# w27-USBIO-v03_rev2_3.net
KiCad netlist of a schematic drawn in EAGLE
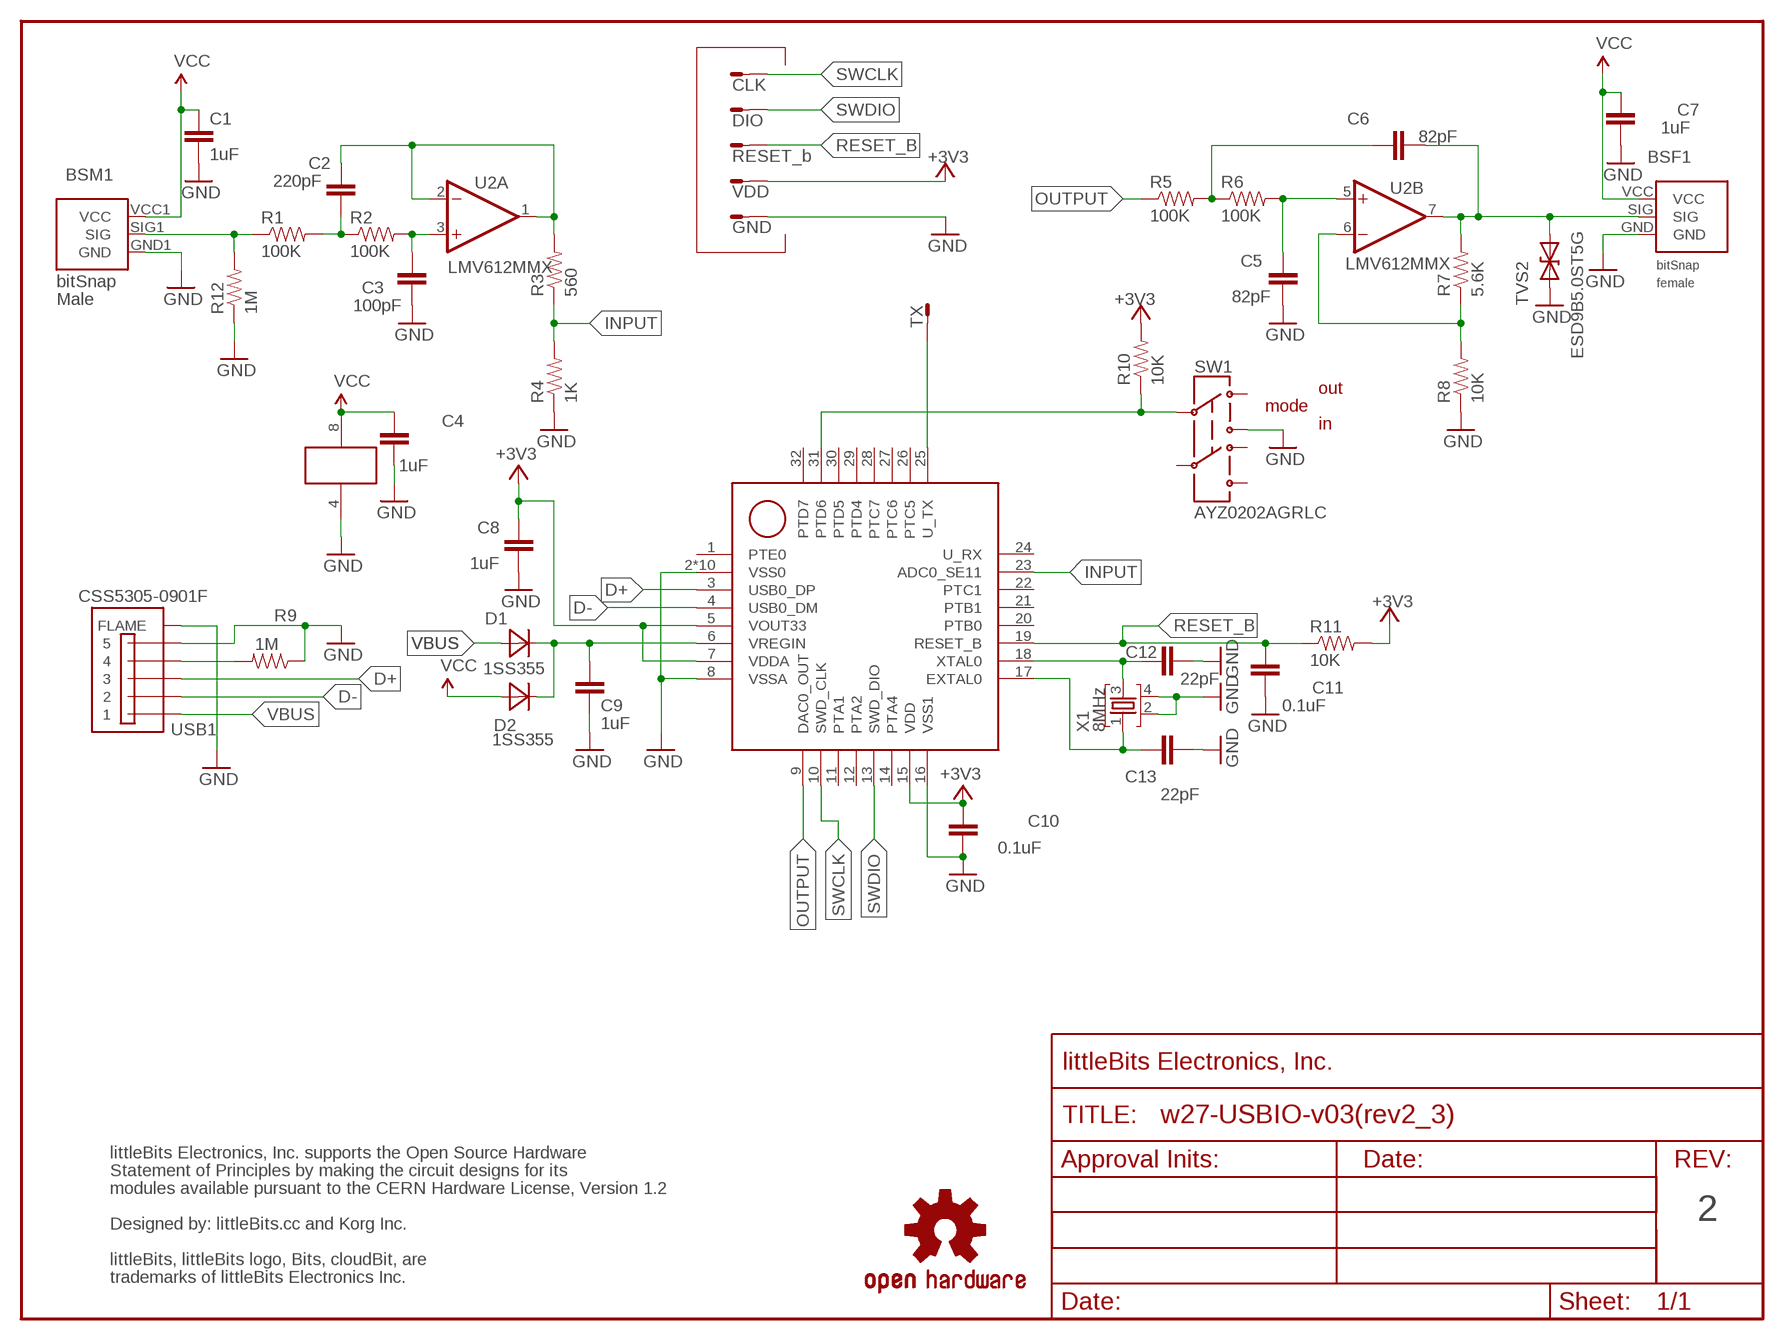
[diagram p0: schematic, sheet 1]

(export (version "E")
  (design (tool "Eeschema 10.0.6"))
  (components
    (comp (ref "BSF1")
      (value "BITSNAP_V03_FEMALE")
      (footprint "eagle-import:BITSNAP_V03_FEMALE")
      (libsource (lib "eagle-import") (part "BITSNAP_V03_FEMALE"))
    )
    (comp (ref "BSM1")
      (value "BITSNAP_V03_MALE")
      (footprint "eagle-import:BITSNAP_V03_MALE")
      (libsource (lib "eagle-import") (part "BITSNAP_V03_MALE"))
    )
    (comp (ref "C1")
      (value "1uF")
      (footprint "eagle-import:CC_1608_0.8_TBR_LB_1PRIMARY")
      (libsource (lib "eagle-import") (part "CC_1608_0.8_TBR_LB_1"))
    )
    (comp (ref "C2")
      (value "220pF")
      (footprint "eagle-import:CC_1608_0.8_TBR_LB_1PRIMARY")
      (libsource (lib "eagle-import") (part "CC_1608_0.8_TBR_LB_1"))
    )
    (comp (ref "C3")
      (value "100pF")
      (footprint "eagle-import:CC_1608_0.8_TBR_LB_1PRIMARY")
      (libsource (lib "eagle-import") (part "CC_1608_0.8_TBR_LB_1"))
    )
    (comp (ref "C4")
      (value "1uF")
      (footprint "eagle-import:CC_1608_0.8_TBR_LB_1PRIMARY")
      (libsource (lib "eagle-import") (part "CC_1608_0.8_TBR_LB_1"))
    )
    (comp (ref "C5")
      (value "82pF")
      (footprint "eagle-import:CC_1608_0.8_TBR_LB_1PRIMARY")
      (libsource (lib "eagle-import") (part "CC_1608_0.8_TBR_LB_1"))
    )
    (comp (ref "C6")
      (value "82pF")
      (footprint "eagle-import:CC_1608_0.8_TBR_LB_1PRIMARY")
      (libsource (lib "eagle-import") (part "CC_1608_0.8_TBR_LB_1"))
    )
    (comp (ref "C7")
      (value "1uF")
      (footprint "eagle-import:CC_1608_0.8_TBR_LB_1PRIMARY")
      (libsource (lib "eagle-import") (part "CC_1608_0.8_TBR_LB_1"))
    )
    (comp (ref "C8")
      (value "1uF")
      (footprint "eagle-import:CC_1608_0.8_TBR_LB_1PRIMARY")
      (libsource (lib "eagle-import") (part "CC_1608_0.8_TBR_LB_1"))
    )
    (comp (ref "C9")
      (value "1uF")
      (footprint "eagle-import:CC_1608_0.8_TBR_LB_1PRIMARY")
      (libsource (lib "eagle-import") (part "CC_1608_0.8_TBR_LB_1"))
    )
    (comp (ref "C10")
      (value "0.1uF")
      (footprint "eagle-import:CC_1608_0.8_TBR_LB_1PRIMARY")
      (libsource (lib "eagle-import") (part "CC_1608_0.8_TBR_LB_1"))
    )
    (comp (ref "C11")
      (value "0.1uF")
      (footprint "eagle-import:CC_1608_0.8_TBR_LB_1PRIMARY")
      (libsource (lib "eagle-import") (part "CC_1608_0.8_TBR_LB_1"))
    )
    (comp (ref "C12")
      (value "22pF")
      (footprint "eagle-import:CC_1608_0.8_TBR_LB_1PRIMARY")
      (libsource (lib "eagle-import") (part "CC_1608_0.8_TBR_LB_1"))
    )
    (comp (ref "C13")
      (value "22pF")
      (footprint "eagle-import:CC_1608_0.8_TBR_LB_1PRIMARY")
      (libsource (lib "eagle-import") (part "CC_1608_0.8_TBR_LB_1"))
    )
    (comp (ref "D1")
      (value "1SS355")
      (footprint "eagle-import:DISC_ROHM-UMD2_#_TBR_LB_1PRIMARY")
      (libsource (lib "eagle-import") (part "DISC_ROHM-UMD2_#_TBR_LB_1"))
    )
    (comp (ref "D2")
      (value "1SS355")
      (footprint "eagle-import:DISC_ROHM-UMD2_#_TBR_LB_1PRIMARY")
      (libsource (lib "eagle-import") (part "DISC_ROHM-UMD2_#_TBR_LB_1"))
    )
    (comp (ref "FRAME1")
      (value "FRAME-LETTER-OHWOHW")
      (footprint "eagle-import:FABDWG01-OHW")
      (libsource (lib "eagle-import") (part "FRAME-LETTER-OHWOHW"))
    )
    (comp (ref "JP1")
      (value "GND")
      (footprint "eagle-import:TEST_POINT_1PRIMARY")
      (libsource (lib "eagle-import") (part "TEST_POINT_1"))
    )
    (comp (ref "JP2")
      (value "VDD")
      (footprint "eagle-import:TEST_POINT_1PRIMARY")
      (libsource (lib "eagle-import") (part "TEST_POINT_1"))
    )
    (comp (ref "JP3")
      (value "RESET_b")
      (footprint "eagle-import:TEST_POINT_1PRIMARY")
      (libsource (lib "eagle-import") (part "TEST_POINT_1"))
    )
    (comp (ref "JP4")
      (value "DIO")
      (footprint "eagle-import:TEST_POINT_1PRIMARY")
      (libsource (lib "eagle-import") (part "TEST_POINT_1"))
    )
    (comp (ref "JP5")
      (value "CLK")
      (footprint "eagle-import:TEST_POINT_1PRIMARY")
      (libsource (lib "eagle-import") (part "TEST_POINT_1"))
    )
    (comp (ref "JP6")
      (value "TX")
      (footprint "eagle-import:TEST_POINT_1PRIMARY")
      (libsource (lib "eagle-import") (part "TEST_POINT_1"))
    )
    (comp (ref "R1")
      (value "100K")
      (footprint "eagle-import:R_1608_LB")
      (libsource (lib "eagle-import") (part "R_1608_LB"))
    )
    (comp (ref "R2")
      (value "100K")
      (footprint "eagle-import:R_1608_LB")
      (libsource (lib "eagle-import") (part "R_1608_LB"))
    )
    (comp (ref "R3")
      (value "560")
      (footprint "eagle-import:R_1608_LB")
      (libsource (lib "eagle-import") (part "R_1608_LB"))
    )
    (comp (ref "R4")
      (value "1K")
      (footprint "eagle-import:R_1608_LB")
      (libsource (lib "eagle-import") (part "R_1608_LB"))
    )
    (comp (ref "R5")
      (value "100K")
      (footprint "eagle-import:R_1608_LB")
      (libsource (lib "eagle-import") (part "R_1608_LB"))
    )
    (comp (ref "R6")
      (value "100K")
      (footprint "eagle-import:R_1608_LB")
      (libsource (lib "eagle-import") (part "R_1608_LB"))
    )
    (comp (ref "R7")
      (value "5.6K")
      (footprint "eagle-import:R_1608_LB")
      (libsource (lib "eagle-import") (part "R_1608_LB"))
    )
    (comp (ref "R8")
      (value "10K")
      (footprint "eagle-import:R_1608_LB")
      (libsource (lib "eagle-import") (part "R_1608_LB"))
    )
    (comp (ref "R9")
      (value "1M")
      (footprint "eagle-import:R_1608_LB")
      (libsource (lib "eagle-import") (part "R_1608_LB"))
    )
    (comp (ref "R10")
      (value "10K")
      (footprint "eagle-import:R_1608_LB")
      (libsource (lib "eagle-import") (part "R_1608_LB"))
    )
    (comp (ref "R11")
      (value "10K")
      (footprint "eagle-import:R_1608_LB")
      (libsource (lib "eagle-import") (part "R_1608_LB"))
    )
    (comp (ref "R12")
      (value "1M")
      (footprint "eagle-import:RES-0402")
      (libsource (lib "eagle-import") (part "RESISTOR0402"))
    )
    (comp (ref "SW1")
      (value "AYZ0202AGRLC")
      (footprint "eagle-import:SW_MS-22C01_#_TBR_LB_1PRIMARY")
      (libsource (lib "eagle-import") (part "SW_MS-22C01_#_TBR_LB_1"))
    )
    (comp (ref "TVS2")
      (value "ESD9B5.0ST5G")
      (footprint "eagle-import:SOD-923")
      (libsource (lib "eagle-import") (part "DIODE-TVSSOD-923"))
    )
    (comp (ref "U$1")
      (value "OSHWCREDIT-KORG")
      (footprint "eagle-import:OSHWCREDIT-KORG")
      (libsource (lib "eagle-import") (part "OSHWCREDIT-KORG"))
    )
    (comp (ref "U$5")
      (value "OSHW-LOGOL")
      (footprint "eagle-import:OSHW-LOGO-L")
      (libsource (lib "eagle-import") (part "OSHW-LOGOL"))
    )
    (comp (ref "U1")
      (value "MKL26Z64VFM4")
      (footprint "eagle-import:IC_TI-QFN32_0.5_TBR_LB_1PRIMARY")
      (libsource (lib "eagle-import") (part "IC_TI-QFN32_0.5_TBR_LB_1"))
    )
    (comp (ref "U2")
      (value "LMV612MMX")
      (footprint "eagle-import:IC_TSSOP8-DCK_0.65_TBR_LB_1PRIMARY")
      (libsource (lib "eagle-import") (part "IC_TSSOP8-DCK_0.65_TBR_LB_1"))
    )
    (comp (ref "USB1")
      (value "CSS5305-0901F")
      (footprint "eagle-import:MICRO-USB-FRONT-DIP-REAR-SMD")
      (libsource (lib "eagle-import") (part "CSS5305-0109F"))
    )
    (comp (ref "X1")
      (value "8MHz")
      (footprint "eagle-import:X_ROSON_RT5_#_TBR_LB_1PRIMARY")
      (libsource (lib "eagle-import") (part "X_ROSON_RT5_#_TBR_LB_1"))
    )
  )
  (nets
    (net (code "1") (name "+3V3") (class "Default")
      (node (ref "C10") (pin "2") (pinfunction "2_2") (pintype "passive"))
      (node (ref "C8") (pin "2") (pinfunction "2_2") (pintype "passive"))
      (node (ref "JP2") (pin "1") (pinfunction "S_1") (pintype "passive"))
      (node (ref "R10") (pin "2") (pinfunction "2_2") (pintype "passive"))
      (node (ref "R11") (pin "2") (pinfunction "2_2") (pintype "passive"))
      (node (ref "U1") (pin "15") (pinfunction "VDD_15") (pintype "bidirectional"))
      (node (ref "U1") (pin "5") (pinfunction "VOUT33_5") (pintype "bidirectional"))
      (node (ref "U1") (pin "7") (pinfunction "VDDA_7") (pintype "bidirectional"))
    )
    (net (code "2") (name "D+") (class "Default")
      (node (ref "U1") (pin "3") (pinfunction "USB0_DP_3") (pintype "bidirectional"))
      (node (ref "USB1") (pin "3") (pinfunction "3_3") (pintype "input"))
    )
    (net (code "3") (name "D-") (class "Default")
      (node (ref "U1") (pin "4") (pinfunction "USB0_DM_4") (pintype "bidirectional"))
      (node (ref "USB1") (pin "2") (pinfunction "2_2") (pintype "input"))
    )
    (net (code "4") (name "GND") (class "Default")
      (node (ref "BSF1") (pin "GND") (pinfunction "GND_GND") (pintype "bidirectional"))
      (node (ref "BSM1") (pin "GND1") (pinfunction "GND_GND1") (pintype "bidirectional"))
      (node (ref "C1") (pin "2") (pinfunction "2_2") (pintype "passive"))
      (node (ref "C10") (pin "1") (pinfunction "1_1") (pintype "passive"))
      (node (ref "C11") (pin "1") (pinfunction "1_1") (pintype "passive"))
      (node (ref "C12") (pin "1") (pinfunction "1_1") (pintype "passive"))
      (node (ref "C13") (pin "1") (pinfunction "1_1") (pintype "passive"))
      (node (ref "C3") (pin "1") (pinfunction "1_1") (pintype "passive"))
      (node (ref "C4") (pin "1") (pinfunction "1_1") (pintype "passive"))
      (node (ref "C5") (pin "1") (pinfunction "1_1") (pintype "passive"))
      (node (ref "C7") (pin "1") (pinfunction "1_1") (pintype "passive"))
      (node (ref "C8") (pin "1") (pinfunction "1_1") (pintype "passive"))
      (node (ref "C9") (pin "2") (pinfunction "2_2") (pintype "passive"))
      (node (ref "JP1") (pin "1") (pinfunction "S_1") (pintype "passive"))
      (node (ref "R12") (pin "1") (pinfunction "1_1") (pintype "passive"))
      (node (ref "R4") (pin "1") (pinfunction "1_1") (pintype "passive"))
      (node (ref "R8") (pin "1") (pinfunction "1_1") (pintype "passive"))
      (node (ref "R9") (pin "1") (pinfunction "1_1") (pintype "passive"))
      (node (ref "SW1") (pin "3") (pinfunction "3_3") (pintype "bidirectional"))
      (node (ref "TVS2") (pin "1") (pinfunction "A_1") (pintype "passive"))
      (node (ref "U1") (pin "16") (pinfunction "VSS1_16") (pintype "bidirectional"))
      (node (ref "U1") (pin "2") (pinfunction "VSS0_2") (pintype "bidirectional"))
      (node (ref "U1") (pin "33") (pinfunction "VSS0_33") (pintype "bidirectional"))
      (node (ref "U1") (pin "34") (pinfunction "VSS0_34") (pintype "bidirectional"))
      (node (ref "U1") (pin "35") (pinfunction "VSS0_35") (pintype "bidirectional"))
      (node (ref "U1") (pin "36") (pinfunction "VSS0_36") (pintype "bidirectional"))
      (node (ref "U1") (pin "37") (pinfunction "VSS0_37") (pintype "bidirectional"))
      (node (ref "U1") (pin "38") (pinfunction "VSS0_38") (pintype "bidirectional"))
      (node (ref "U1") (pin "39") (pinfunction "VSS0_39") (pintype "bidirectional"))
      (node (ref "U1") (pin "40") (pinfunction "VSS0_40") (pintype "bidirectional"))
      (node (ref "U1") (pin "41") (pinfunction "VSS0_41") (pintype "bidirectional"))
      (node (ref "U1") (pin "8") (pinfunction "VSSA_8") (pintype "bidirectional"))
      (node (ref "U2") (pin "4") (pinfunction "V-_4") (pintype "power_in"))
      (node (ref "USB1") (pin "10") (pinfunction "FLAME_10") (pintype "power_in"))
      (node (ref "USB1") (pin "11") (pinfunction "FLAME_11") (pintype "power_in"))
      (node (ref "USB1") (pin "5") (pinfunction "5_5") (pintype "input"))
      (node (ref "USB1") (pin "6") (pinfunction "FLAME_6") (pintype "power_in"))
      (node (ref "USB1") (pin "7") (pinfunction "FLAME_7") (pintype "power_in"))
      (node (ref "USB1") (pin "8") (pinfunction "FLAME_8") (pintype "power_in"))
      (node (ref "USB1") (pin "9") (pinfunction "FLAME_9") (pintype "power_in"))
      (node (ref "X1") (pin "2") (pinfunction "2_2") (pintype "passive"))
      (node (ref "X1") (pin "4") (pinfunction "4_4") (pintype "passive"))
    )
    (net (code "5") (name "INPUT") (class "Default")
      (node (ref "R3") (pin "1") (pinfunction "1_1") (pintype "passive"))
      (node (ref "R4") (pin "2") (pinfunction "2_2") (pintype "passive"))
      (node (ref "U1") (pin "23") (pinfunction "ADC0_SE11_23") (pintype "bidirectional"))
    )
    (net (code "6") (name "Net-(BSM1-SIG)") (class "Default")
      (node (ref "BSM1") (pin "SIG1") (pinfunction "SIG_SIG1") (pintype "bidirectional"))
      (node (ref "R1") (pin "1") (pinfunction "1_1") (pintype "passive"))
      (node (ref "R12") (pin "2") (pinfunction "2_2") (pintype "passive"))
    )
    (net (code "7") (name "Net-(C2-Pad1)") (class "Default")
      (node (ref "C2") (pin "1") (pinfunction "1_1") (pintype "passive"))
      (node (ref "R1") (pin "2") (pinfunction "2_2") (pintype "passive"))
      (node (ref "R2") (pin "1") (pinfunction "1_1") (pintype "passive"))
    )
    (net (code "8") (name "Net-(C6-Pad1)") (class "Default")
      (node (ref "C6") (pin "1") (pinfunction "1_1") (pintype "passive"))
      (node (ref "R5") (pin "2") (pinfunction "2_2") (pintype "passive"))
      (node (ref "R6") (pin "1") (pinfunction "1_1") (pintype "passive"))
    )
    (net (code "9") (name "Net-(JP6-S)") (class "Default")
      (node (ref "JP6") (pin "1") (pinfunction "S_1") (pintype "passive"))
      (node (ref "U1") (pin "25") (pinfunction "U_TX_25") (pintype "bidirectional"))
    )
    (net (code "10") (name "Net-(R9-Pad2)") (class "Default")
      (node (ref "R9") (pin "2") (pinfunction "2_2") (pintype "passive"))
      (node (ref "USB1") (pin "4") (pinfunction "4_4") (pintype "input"))
    )
    (net (code "11") (name "Net-(TVS2-C)") (class "Default")
      (node (ref "BSF1") (pin "SIG") (pinfunction "SIG_SIG") (pintype "bidirectional"))
      (node (ref "C6") (pin "2") (pinfunction "2_2") (pintype "passive"))
      (node (ref "R7") (pin "2") (pinfunction "2_2") (pintype "passive"))
      (node (ref "TVS2") (pin "2") (pinfunction "C_2") (pintype "passive"))
      (node (ref "U2") (pin "7") (pinfunction "OUT_7") (pintype "output"))
    )
    (net (code "12") (name "Net-(U1-EXTAL0)") (class "Default")
      (node (ref "C13") (pin "2") (pinfunction "2_2") (pintype "passive"))
      (node (ref "U1") (pin "17") (pinfunction "EXTAL0_17") (pintype "bidirectional"))
      (node (ref "X1") (pin "1") (pinfunction "1_1") (pintype "passive"))
    )
    (net (code "13") (name "Net-(U1-PTD6)") (class "Default")
      (node (ref "R10") (pin "1") (pinfunction "1_1") (pintype "passive"))
      (node (ref "SW1") (pin "2") (pinfunction "2_2") (pintype "bidirectional"))
      (node (ref "U1") (pin "31") (pinfunction "PTD6_31") (pintype "bidirectional"))
    )
    (net (code "14") (name "Net-(U1-VREGIN)") (class "Default")
      (node (ref "C9") (pin "1") (pinfunction "1_1") (pintype "passive"))
      (node (ref "D1") (pin "2") (pinfunction "2_2") (pintype "passive"))
      (node (ref "D2") (pin "2") (pinfunction "2_2") (pintype "passive"))
      (node (ref "U1") (pin "6") (pinfunction "VREGIN_6") (pintype "bidirectional"))
    )
    (net (code "15") (name "Net-(U1-XTAL0)") (class "Default")
      (node (ref "C12") (pin "2") (pinfunction "2_2") (pintype "passive"))
      (node (ref "U1") (pin "18") (pinfunction "XTAL0_18") (pintype "bidirectional"))
      (node (ref "X1") (pin "3") (pinfunction "3_3") (pintype "passive"))
    )
    (net (code "16") (name "Net-(U2A-+IN)") (class "Default")
      (node (ref "C3") (pin "2") (pinfunction "2_2") (pintype "passive"))
      (node (ref "R2") (pin "2") (pinfunction "2_2") (pintype "passive"))
      (node (ref "U2") (pin "3") (pinfunction "+IN_3") (pintype "input"))
    )
    (net (code "17") (name "Net-(U2A--IN)") (class "Default")
      (node (ref "C2") (pin "2") (pinfunction "2_2") (pintype "passive"))
      (node (ref "R3") (pin "2") (pinfunction "2_2") (pintype "passive"))
      (node (ref "U2") (pin "1") (pinfunction "OUT_1") (pintype "output"))
      (node (ref "U2") (pin "2") (pinfunction "-IN_2") (pintype "input"))
    )
    (net (code "18") (name "Net-(U2B-+IN)") (class "Default")
      (node (ref "C5") (pin "2") (pinfunction "2_2") (pintype "passive"))
      (node (ref "R6") (pin "2") (pinfunction "2_2") (pintype "passive"))
      (node (ref "U2") (pin "5") (pinfunction "+IN_5") (pintype "input"))
    )
    (net (code "19") (name "Net-(U2B--IN)") (class "Default")
      (node (ref "R7") (pin "1") (pinfunction "1_1") (pintype "passive"))
      (node (ref "R8") (pin "2") (pinfunction "2_2") (pintype "passive"))
      (node (ref "U2") (pin "6") (pinfunction "-IN_6") (pintype "input"))
    )
    (net (code "20") (name "OUTPUT") (class "Default")
      (node (ref "R5") (pin "1") (pinfunction "1_1") (pintype "passive"))
      (node (ref "U1") (pin "9") (pinfunction "DAC0_OUT_9") (pintype "bidirectional"))
    )
    (net (code "21") (name "RESET_B") (class "Default")
      (node (ref "C11") (pin "2") (pinfunction "2_2") (pintype "passive"))
      (node (ref "JP3") (pin "1") (pinfunction "S_1") (pintype "passive"))
      (node (ref "R11") (pin "1") (pinfunction "1_1") (pintype "passive"))
      (node (ref "U1") (pin "19") (pinfunction "RESET_B_19") (pintype "bidirectional"))
    )
    (net (code "22") (name "SWCLK") (class "Default")
      (node (ref "JP5") (pin "1") (pinfunction "S_1") (pintype "passive"))
      (node (ref "U1") (pin "10") (pinfunction "SWD_CLK_10") (pintype "bidirectional"))
    )
    (net (code "23") (name "SWDIO") (class "Default")
      (node (ref "JP4") (pin "1") (pinfunction "S_1") (pintype "passive"))
      (node (ref "U1") (pin "13") (pinfunction "SWD_DIO_13") (pintype "bidirectional"))
    )
    (net (code "24") (name "VBUS") (class "Default")
      (node (ref "D1") (pin "1") (pinfunction "1_1") (pintype "passive"))
      (node (ref "USB1") (pin "1") (pinfunction "1_1") (pintype "input"))
    )
    (net (code "25") (name "VCC") (class "Default")
      (node (ref "BSF1") (pin "VCC") (pinfunction "VCC_VCC") (pintype "bidirectional"))
      (node (ref "BSM1") (pin "VCC1") (pinfunction "VCC_VCC1") (pintype "bidirectional"))
      (node (ref "C1") (pin "1") (pinfunction "1_1") (pintype "passive"))
      (node (ref "C4") (pin "2") (pinfunction "2_2") (pintype "passive"))
      (node (ref "C7") (pin "2") (pinfunction "2_2") (pintype "passive"))
      (node (ref "D2") (pin "1") (pinfunction "1_1") (pintype "passive"))
      (node (ref "U2") (pin "8") (pinfunction "V+_8") (pintype "power_in"))
    )
    (net (code "26") (name "unconnected-(SW1-Pad1)") (class "Default")
      (node (ref "SW1") (pin "1") (pinfunction "1_1") (pintype "bidirectional"))
    )
    (net (code "27") (name "unconnected-(SW1-Pad4)") (class "Default")
      (node (ref "SW1") (pin "4") (pinfunction "4_4") (pintype "bidirectional"))
    )
    (net (code "28") (name "unconnected-(SW1-Pad5)") (class "Default")
      (node (ref "SW1") (pin "5") (pinfunction "5_5") (pintype "bidirectional"))
    )
    (net (code "29") (name "unconnected-(SW1-Pad6)") (class "Default")
      (node (ref "SW1") (pin "6") (pinfunction "6_6") (pintype "bidirectional"))
    )
    (net (code "30") (name "unconnected-(U1-PTA1-Pad11)") (class "Default")
      (node (ref "U1") (pin "11") (pinfunction "PTA1_11") (pintype "bidirectional"))
    )
    (net (code "31") (name "unconnected-(U1-PTA2-Pad12)") (class "Default")
      (node (ref "U1") (pin "12") (pinfunction "PTA2_12") (pintype "bidirectional"))
    )
    (net (code "32") (name "unconnected-(U1-PTA4-Pad14)") (class "Default")
      (node (ref "U1") (pin "14") (pinfunction "PTA4_14") (pintype "bidirectional"))
    )
    (net (code "33") (name "unconnected-(U1-PTB0-Pad20)") (class "Default")
      (node (ref "U1") (pin "20") (pinfunction "PTB0_20") (pintype "bidirectional"))
    )
    (net (code "34") (name "unconnected-(U1-PTB1-Pad21)") (class "Default")
      (node (ref "U1") (pin "21") (pinfunction "PTB1_21") (pintype "bidirectional"))
    )
    (net (code "35") (name "unconnected-(U1-PTC1-Pad22)") (class "Default")
      (node (ref "U1") (pin "22") (pinfunction "PTC1_22") (pintype "bidirectional"))
    )
    (net (code "36") (name "unconnected-(U1-PTC5-Pad26)") (class "Default")
      (node (ref "U1") (pin "26") (pinfunction "PTC5_26") (pintype "bidirectional"))
    )
    (net (code "37") (name "unconnected-(U1-PTC6-Pad27)") (class "Default")
      (node (ref "U1") (pin "27") (pinfunction "PTC6_27") (pintype "bidirectional"))
    )
    (net (code "38") (name "unconnected-(U1-PTC7-Pad28)") (class "Default")
      (node (ref "U1") (pin "28") (pinfunction "PTC7_28") (pintype "bidirectional"))
    )
    (net (code "39") (name "unconnected-(U1-PTD4-Pad29)") (class "Default")
      (node (ref "U1") (pin "29") (pinfunction "PTD4_29") (pintype "bidirectional"))
    )
    (net (code "40") (name "unconnected-(U1-PTD5-Pad30)") (class "Default")
      (node (ref "U1") (pin "30") (pinfunction "PTD5_30") (pintype "bidirectional"))
    )
    (net (code "41") (name "unconnected-(U1-PTD7-Pad32)") (class "Default")
      (node (ref "U1") (pin "32") (pinfunction "PTD7_32") (pintype "bidirectional"))
    )
    (net (code "42") (name "unconnected-(U1-PTE0-Pad1)") (class "Default")
      (node (ref "U1") (pin "1") (pinfunction "PTE0_1") (pintype "bidirectional"))
    )
    (net (code "43") (name "unconnected-(U1-U_RX-Pad24)") (class "Default")
      (node (ref "U1") (pin "24") (pinfunction "U_RX_24") (pintype "bidirectional"))
    )
  )
)
